# 4ch_lpc.net
KiCad netlist of a schematic drawn in EAGLE
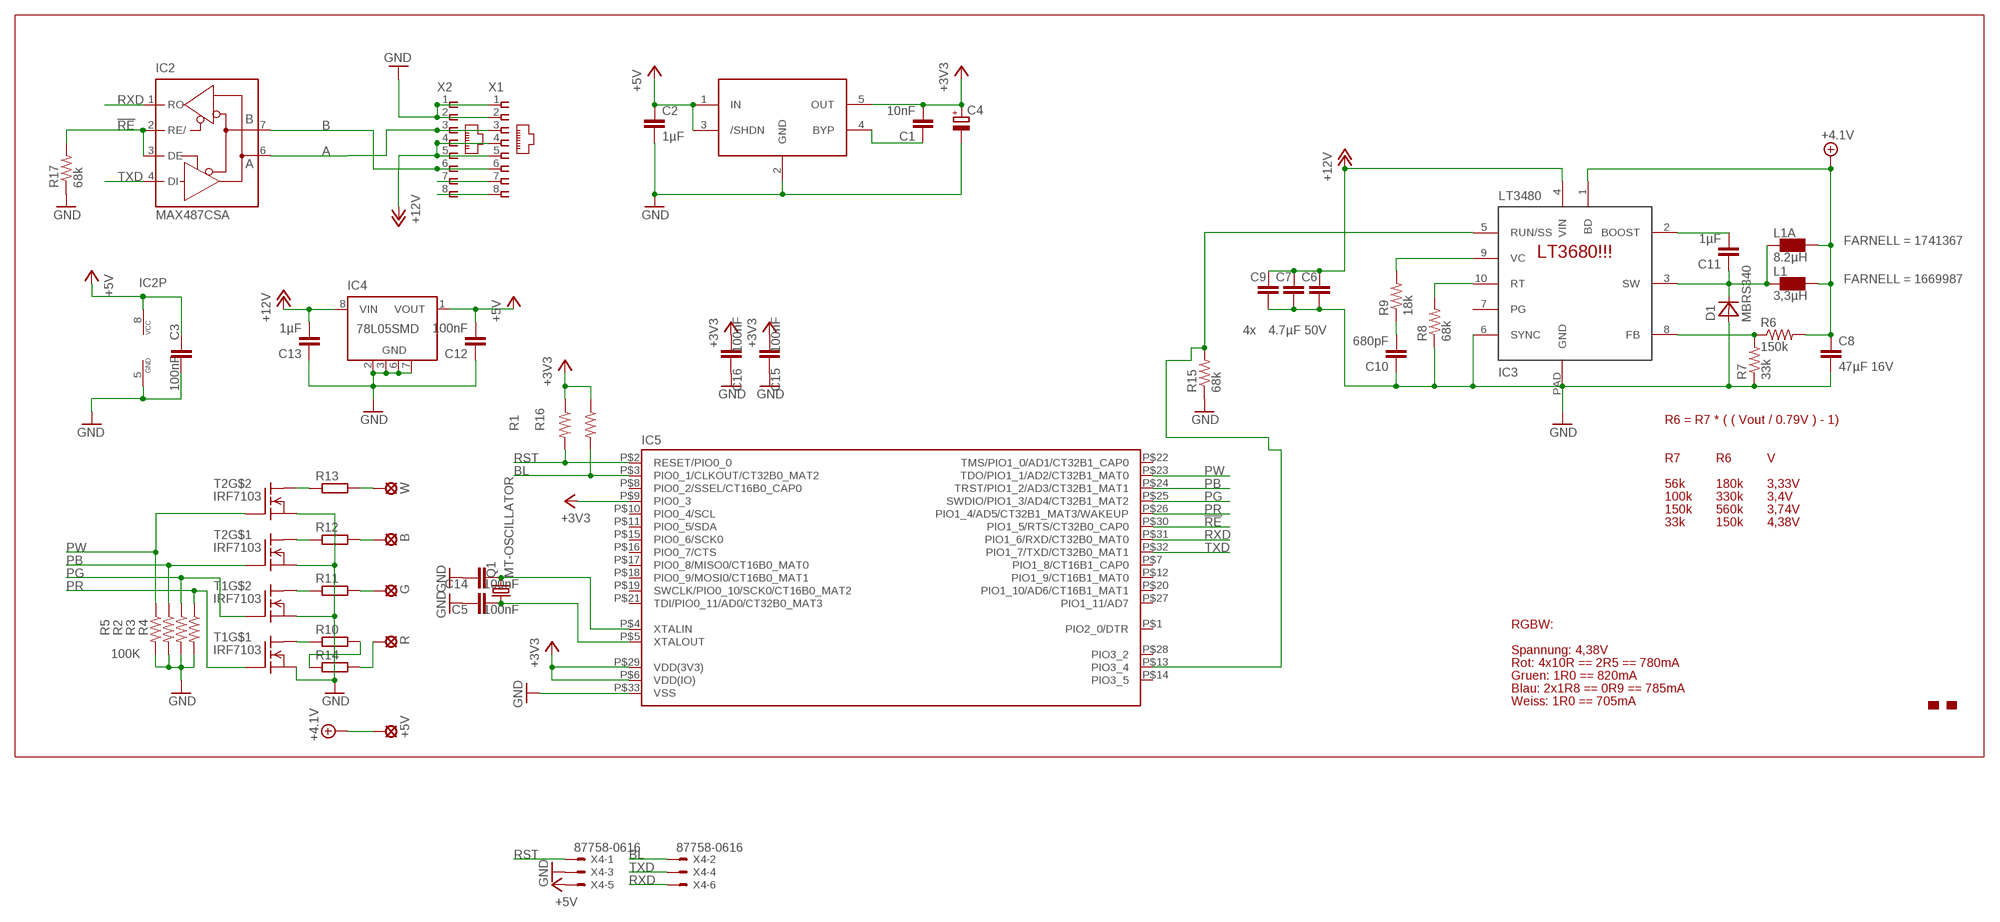
[diagram p0: schematic, sheet 1]

(export (version "E")
  (design (tool "Eeschema 10.0.6"))
  (components
    (comp (ref "+5V")
      (value "SE14")
      (footprint "eagle-import:SE14")
      (libsource (lib "eagle-import") (part "SE14"))
    )
    (comp (ref "B")
      (value "SE14")
      (footprint "eagle-import:SE14")
      (libsource (lib "eagle-import") (part "SE14"))
    )
    (comp (ref "C1")
      (value "10nF")
      (footprint "eagle-import:C0402")
      (libsource (lib "eagle-import") (part "C-EUC0402"))
    )
    (comp (ref "C2")
      (value "1µF")
      (footprint "eagle-import:0805")
      (libsource (lib "eagle-import") (part "SparkFun-Capacitors_CAP0805"))
    )
    (comp (ref "C3")
      (value "100nF")
      (footprint "eagle-import:0402-CAP")
      (libsource (lib "eagle-import") (part "CAP0402-CAP"))
    )
    (comp (ref "C4")
      (value "CPOL-EUSMCA")
      (footprint "eagle-import:SMC_A")
      (libsource (lib "eagle-import") (part "CPOL-EUSMCA"))
    )
    (comp (ref "C5")
      (value "100nF")
      (footprint "eagle-import:0402-CAP")
      (libsource (lib "eagle-import") (part "CAP0402-CAP"))
    )
    (comp (ref "C6")
      (value "4.7µF 50V")
      (footprint "eagle-import:1210")
      (libsource (lib "eagle-import") (part "CAP1210"))
    )
    (comp (ref "C7")
      (value "4.7µF 50V")
      (footprint "eagle-import:1210")
      (libsource (lib "eagle-import") (part "CAP1210"))
    )
    (comp (ref "C8")
      (value "47µF 16V")
      (footprint "eagle-import:1210")
      (libsource (lib "eagle-import") (part "CAP1210"))
    )
    (comp (ref "C9")
      (value "4.7µF 50V")
      (footprint "eagle-import:1210")
      (libsource (lib "eagle-import") (part "CAP1210"))
    )
    (comp (ref "C10")
      (value "680pF")
      (footprint "eagle-import:0805")
      (libsource (lib "eagle-import") (part "CAP0805"))
    )
    (comp (ref "C11")
      (value "1µF")
      (footprint "eagle-import:0805")
      (libsource (lib "eagle-import") (part "CAP0805"))
    )
    (comp (ref "C12")
      (value "100nF")
      (footprint "eagle-import:0402-CAP")
      (libsource (lib "eagle-import") (part "CAP0402-CAP"))
    )
    (comp (ref "C13")
      (value "1µF")
      (footprint "eagle-import:0805")
      (libsource (lib "eagle-import") (part "CAP0805"))
    )
    (comp (ref "C14")
      (value "100nF")
      (footprint "eagle-import:0402-CAP")
      (libsource (lib "eagle-import") (part "CAP0402-CAP"))
    )
    (comp (ref "C15")
      (value "100nF")
      (footprint "eagle-import:0402-CAP")
      (libsource (lib "eagle-import") (part "CAP0402-CAP"))
    )
    (comp (ref "C16")
      (value "100nF")
      (footprint "eagle-import:0402-CAP")
      (libsource (lib "eagle-import") (part "CAP0402-CAP"))
    )
    (comp (ref "D1")
      (value "MBRS340")
      (footprint "eagle-import:DO214AB")
      (libsource (lib "eagle-import") (part "MBRS340"))
    )
    (comp (ref "G")
      (value "SE14")
      (footprint "eagle-import:SE14")
      (libsource (lib "eagle-import") (part "SE14"))
    )
    (comp (ref "IC1")
      (value "LT1761")
      (footprint "eagle-import:SOT23-5L")
      (libsource (lib "eagle-import") (part "LT1761"))
    )
    (comp (ref "IC2")
      (value "MAX487CSA")
      (footprint "eagle-import:SO08")
      (fields (field (name "MF") "MAXIM") (field (name "MPN") "MAX481CSA"))
      (libsource (lib "eagle-import") (part "MAX481CSA"))
    )
    (comp (ref "IC3")
      (value "LT3972")
      (footprint "eagle-import:MSOP10-PAD")
      (libsource (lib "eagle-import") (part "LT3480"))
    )
    (comp (ref "IC4")
      (value "78L05SMD")
      (footprint "eagle-import:SO08")
      (libsource (lib "eagle-import") (part "78LSMD05"))
    )
    (comp (ref "IC5")
      (value "LPC1113/4_QFN")
      (footprint "eagle-import:HVQFN33-7X7")
      (fields (field (name "MANF") "NXP"))
      (libsource (lib "eagle-import") (part "LPC1113/4_QFN"))
    )
    (comp (ref "L1")
      (value "3,3µH")
      (footprint "eagle-import:RLF7030")
      (fields (field (name "FARNELL") "1669987"))
      (libsource (lib "eagle-import") (part "TDK_RLF7030"))
    )
    (comp (ref "L1A")
      (value "8.2µH")
      (footprint "eagle-import:IHLP-2525CZ")
      (fields (field (name "FARNELL") "1741367"))
      (libsource (lib "eagle-import") (part "IHLP-2525CZ"))
    )
    (comp (ref "Q1")
      (value "MT-OSCILLATOR")
      (footprint "eagle-import:MT")
      (libsource (lib "eagle-import") (part "MT-OSCILLATOR"))
    )
    (comp (ref "R")
      (value "SE14")
      (footprint "eagle-import:SE14")
      (libsource (lib "eagle-import") (part "SE14"))
    )
    (comp (ref "R1")
      (value "100K")
      (footprint "eagle-import:0402-RES")
      (libsource (lib "eagle-import") (part "RESISTOR0402-RES"))
    )
    (comp (ref "R2")
      (value "100K")
      (footprint "eagle-import:0402-RES")
      (libsource (lib "eagle-import") (part "RESISTOR0402-RES"))
    )
    (comp (ref "R3")
      (value "100K")
      (footprint "eagle-import:0402-RES")
      (libsource (lib "eagle-import") (part "RESISTOR0402-RES"))
    )
    (comp (ref "R4")
      (value "100K")
      (footprint "eagle-import:0402-RES")
      (libsource (lib "eagle-import") (part "RESISTOR0402-RES"))
    )
    (comp (ref "R5")
      (value "100K")
      (footprint "eagle-import:0402-RES")
      (libsource (lib "eagle-import") (part "RESISTOR0402-RES"))
    )
    (comp (ref "R6")
      (value "150k")
      (footprint "eagle-import:0805")
      (libsource (lib "eagle-import") (part "RESISTOR0805-RES"))
    )
    (comp (ref "R7")
      (value "33k")
      (footprint "eagle-import:0805")
      (libsource (lib "eagle-import") (part "RESISTOR0805-RES"))
    )
    (comp (ref "R8")
      (value "68k")
      (footprint "eagle-import:0805")
      (libsource (lib "eagle-import") (part "RESISTOR0805-RES"))
    )
    (comp (ref "R9")
      (value "18k")
      (footprint "eagle-import:0805")
      (libsource (lib "eagle-import") (part "RESISTOR0805-RES"))
    )
    (comp (ref "R10")
      (value "R-EU_MELF0207R")
      (footprint "eagle-import:MINI_MELF-0207R")
      (libsource (lib "eagle-import") (part "R-EU_MELF0207R"))
    )
    (comp (ref "R11")
      (value "R-EU_MELF0207R")
      (footprint "eagle-import:MINI_MELF-0207R")
      (libsource (lib "eagle-import") (part "R-EU_MELF0207R"))
    )
    (comp (ref "R12")
      (value "R-EU_MELF0207R")
      (footprint "eagle-import:MINI_MELF-0207R")
      (libsource (lib "eagle-import") (part "R-EU_MELF0207R"))
    )
    (comp (ref "R13")
      (value "R-EU_MELF0207R")
      (footprint "eagle-import:MINI_MELF-0207R")
      (libsource (lib "eagle-import") (part "R-EU_MELF0207R"))
    )
    (comp (ref "R14")
      (value "R-EU_MELF0207R")
      (footprint "eagle-import:MINI_MELF-0207R")
      (libsource (lib "eagle-import") (part "R-EU_MELF0207R"))
    )
    (comp (ref "R15")
      (value "68k")
      (footprint "eagle-import:0402-RES")
      (libsource (lib "eagle-import") (part "RESISTOR0402-RES"))
    )
    (comp (ref "R16")
      (value "100K")
      (footprint "eagle-import:0402-RES")
      (libsource (lib "eagle-import") (part "RESISTOR0402-RES"))
    )
    (comp (ref "R17")
      (value "68k")
      (footprint "eagle-import:0402-RES")
      (libsource (lib "eagle-import") (part "RESISTOR0402-RES"))
    )
    (comp (ref "T1")
      (value "IRF7103")
      (footprint "eagle-import:SO-8")
      (libsource (lib "eagle-import") (part "IRF7103"))
    )
    (comp (ref "T2")
      (value "IRF7103")
      (footprint "eagle-import:SO-8")
      (libsource (lib "eagle-import") (part "IRF7103"))
    )
    (comp (ref "U$1")
      (value "MAKE-DD_LOGO'PROMPT'")
      (footprint "eagle-import:MAKE-DD_LOGO_PROMPT")
      (libsource (lib "eagle-import") (part "MAKE-DD_LOGO'PROMPT'"))
    )
    (comp (ref "W")
      (value "SE14")
      (footprint "eagle-import:SE14")
      (libsource (lib "eagle-import") (part "SE14"))
    )
    (comp (ref "X1")
      (value "RJ45-8L-B")
      (footprint "eagle-import:RJ45-NO-SHIELD")
      (fields (field (name "MF") "TYCO ELECTRONICS"))
      (libsource (lib "eagle-import") (part "RJ45-8L-B"))
    )
    (comp (ref "X2")
      (value "RJ45-8L-B")
      (footprint "eagle-import:RJ45-NO-SHIELD")
      (fields (field (name "MF") "TYCO ELECTRONICS"))
      (libsource (lib "eagle-import") (part "RJ45-8L-B"))
    )
    (comp (ref "X4")
      (value "87758-0616")
      (footprint "eagle-import:87758-0616")
      (libsource (lib "eagle-import") (part "87758-0616"))
    )
  )
  (nets
    (net (code "1") (name "+3V3") (class "Default")
      (node (ref "C1") (pin "2") (pinfunction "2_2") (pintype "passive"))
      (node (ref "C15") (pin "2") (pinfunction "2_2") (pintype "passive"))
      (node (ref "C16") (pin "2") (pinfunction "2_2") (pintype "passive"))
      (node (ref "C4") (pin "+") (pinfunction "+_+") (pintype "passive"))
      (node (ref "IC1") (pin "5") (pinfunction "OUT_5") (pintype "bidirectional"))
      (node (ref "IC5") (pin "P$29") (pinfunction "VDD(3V3)_P$29") (pintype "power_in"))
      (node (ref "IC5") (pin "P$6") (pinfunction "VDD(IO)_P$6") (pintype "power_in"))
      (node (ref "IC5") (pin "P$9") (pinfunction "PIO0_3_P$9") (pintype "bidirectional"))
      (node (ref "R1") (pin "1") (pinfunction "1_1") (pintype "passive"))
      (node (ref "R16") (pin "1") (pinfunction "1_1") (pintype "passive"))
    )
    (net (code "2") (name "+4.1V") (class "Default")
      (node (ref "+5V") (pin "MP") (pinfunction "MP_MP") (pintype "passive"))
      (node (ref "C8") (pin "1") (pinfunction "1_1") (pintype "passive"))
      (node (ref "IC3") (pin "1") (pinfunction "BD_1") (pintype "bidirectional"))
      (node (ref "L1") (pin "P$1") (pinfunction "1_P$1") (pintype "passive"))
      (node (ref "L1A") (pin "P$1") (pinfunction "1_P$1") (pintype "passive"))
      (node (ref "R6") (pin "2") (pinfunction "2_2") (pintype "passive"))
    )
    (net (code "3") (name "+5V") (class "Default")
      (node (ref "C12") (pin "2") (pinfunction "2_2") (pintype "passive"))
      (node (ref "C2") (pin "1") (pinfunction "1_1") (pintype "passive"))
      (node (ref "C3") (pin "1") (pinfunction "1_1") (pintype "passive"))
      (node (ref "IC1") (pin "1") (pinfunction "IN_1") (pintype "bidirectional"))
      (node (ref "IC1") (pin "3") (pinfunction "/SHDN_3") (pintype "bidirectional"))
      (node (ref "IC2") (pin "8") (pinfunction "VCC_8") (pintype "power_in"))
      (node (ref "IC4") (pin "1") (pinfunction "VOUT_1") (pintype "output"))
      (node (ref "X4") (pin "5") (pinfunction "S_5") (pintype "passive"))
    )
    (net (code "4") (name "+12V") (class "Default")
      (node (ref "C13") (pin "2") (pinfunction "2_2") (pintype "passive"))
      (node (ref "C6") (pin "1") (pinfunction "1_1") (pintype "passive"))
      (node (ref "C7") (pin "1") (pinfunction "1_1") (pintype "passive"))
      (node (ref "C9") (pin "1") (pinfunction "1_1") (pintype "passive"))
      (node (ref "IC3") (pin "4") (pinfunction "VIN_4") (pintype "bidirectional"))
      (node (ref "IC4") (pin "8") (pinfunction "VIN_8") (pintype "passive"))
      (node (ref "X1") (pin "4") (pinfunction "4_4") (pintype "passive"))
      (node (ref "X1") (pin "5") (pinfunction "5_5") (pintype "passive"))
      (node (ref "X2") (pin "4") (pinfunction "4_4") (pintype "passive"))
      (node (ref "X2") (pin "5") (pinfunction "5_5") (pintype "passive"))
    )
    (net (code "5") (name "/A") (class "Default")
      (node (ref "IC2") (pin "6") (pinfunction "A_6") (pintype "passive"))
      (node (ref "X1") (pin "3") (pinfunction "3_3") (pintype "passive"))
      (node (ref "X2") (pin "3") (pinfunction "3_3") (pintype "passive"))
    )
    (net (code "6") (name "/B") (class "Default")
      (node (ref "IC2") (pin "7") (pinfunction "B_7") (pintype "passive"))
      (node (ref "X1") (pin "6") (pinfunction "6_6") (pintype "passive"))
      (node (ref "X2") (pin "6") (pinfunction "6_6") (pintype "passive"))
    )
    (net (code "7") (name "/BL") (class "Default")
      (node (ref "IC5") (pin "P$3") (pinfunction "PIO0_1/CLKOUT/CT32B0_MAT2_P$3") (pintype "bidirectional"))
      (node (ref "R16") (pin "2") (pinfunction "2_2") (pintype "passive"))
      (node (ref "X4") (pin "2") (pinfunction "S_2") (pintype "passive"))
    )
    (net (code "8") (name "/PB") (class "Default")
      (node (ref "IC5") (pin "P$24") (pinfunction "TRST/PIO1_2/AD3/CT32B1_MAT1_P$24") (pintype "bidirectional"))
      (node (ref "R2") (pin "1") (pinfunction "1_1") (pintype "passive"))
      (node (ref "T2") (pin "2") (pinfunction "G_2") (pintype "passive"))
    )
    (net (code "9") (name "/PG") (class "Default")
      (node (ref "IC5") (pin "P$25") (pinfunction "SWDIO/PIO1_3/AD4/CT32B1_MAT2_P$25") (pintype "bidirectional"))
      (node (ref "R3") (pin "1") (pinfunction "1_1") (pintype "passive"))
      (node (ref "T1") (pin "4") (pinfunction "G_4") (pintype "passive"))
    )
    (net (code "10") (name "/PR") (class "Default")
      (node (ref "IC5") (pin "P$26") (pinfunction "PIO1_4/AD5/CT32B1_MAT3/WAKEUP_P$26") (pintype "bidirectional"))
      (node (ref "R4") (pin "1") (pinfunction "1_1") (pintype "passive"))
      (node (ref "T1") (pin "2") (pinfunction "G_2") (pintype "passive"))
    )
    (net (code "11") (name "/PW") (class "Default")
      (node (ref "IC5") (pin "P$23") (pinfunction "TDO/PIO1_1/AD2/CT32B1_MAT0_P$23") (pintype "bidirectional"))
      (node (ref "R5") (pin "1") (pinfunction "1_1") (pintype "passive"))
      (node (ref "T2") (pin "4") (pinfunction "G_4") (pintype "passive"))
    )
    (net (code "12") (name "/RST") (class "Default")
      (node (ref "IC5") (pin "P$2") (pinfunction "RESET/PIO0_0_P$2") (pintype "bidirectional"))
      (node (ref "R1") (pin "2") (pinfunction "2_2") (pintype "passive"))
      (node (ref "X4") (pin "1") (pinfunction "S_1") (pintype "passive"))
    )
    (net (code "13") (name "/RXD") (class "Default")
      (node (ref "IC2") (pin "1") (pinfunction "RO_1") (pintype "output"))
      (node (ref "IC5") (pin "P$31") (pinfunction "PIO1_6/RXD/CT32B0_MAT0_P$31") (pintype "bidirectional"))
      (node (ref "X4") (pin "6") (pinfunction "S_6") (pintype "passive"))
    )
    (net (code "14") (name "/TXD") (class "Default")
      (node (ref "IC2") (pin "4") (pinfunction "DI_4") (pintype "input"))
      (node (ref "IC5") (pin "P$32") (pinfunction "PIO1_7/TXD/CT32B0_MAT1_P$32") (pintype "bidirectional"))
      (node (ref "X4") (pin "4") (pinfunction "S_4") (pintype "passive"))
    )
    (net (code "15") (name "/~{RE}") (class "Default")
      (node (ref "IC2") (pin "2") (pinfunction "RE/_2") (pintype "input"))
      (node (ref "IC2") (pin "3") (pinfunction "DE_3") (pintype "input"))
      (node (ref "IC5") (pin "P$30") (pinfunction "PIO1_5/RTS/CT32B0_CAP0_P$30") (pintype "bidirectional"))
      (node (ref "R17") (pin "2") (pinfunction "2_2") (pintype "passive"))
    )
    (net (code "16") (name "GND") (class "Default")
      (node (ref "C10") (pin "1") (pinfunction "1_1") (pintype "passive"))
      (node (ref "C12") (pin "1") (pinfunction "1_1") (pintype "passive"))
      (node (ref "C13") (pin "1") (pinfunction "1_1") (pintype "passive"))
      (node (ref "C14") (pin "1") (pinfunction "1_1") (pintype "passive"))
      (node (ref "C15") (pin "1") (pinfunction "1_1") (pintype "passive"))
      (node (ref "C16") (pin "1") (pinfunction "1_1") (pintype "passive"))
      (node (ref "C2") (pin "2") (pinfunction "2_2") (pintype "passive"))
      (node (ref "C3") (pin "2") (pinfunction "2_2") (pintype "passive"))
      (node (ref "C4") (pin "-") (pinfunction "-_-") (pintype "passive"))
      (node (ref "C5") (pin "1") (pinfunction "1_1") (pintype "passive"))
      (node (ref "C6") (pin "2") (pinfunction "2_2") (pintype "passive"))
      (node (ref "C7") (pin "2") (pinfunction "2_2") (pintype "passive"))
      (node (ref "C8") (pin "2") (pinfunction "2_2") (pintype "passive"))
      (node (ref "C9") (pin "2") (pinfunction "2_2") (pintype "passive"))
      (node (ref "D1") (pin "A") (pinfunction "A_A") (pintype "passive"))
      (node (ref "IC1") (pin "2") (pinfunction "GND_2") (pintype "bidirectional"))
      (node (ref "IC2") (pin "5") (pinfunction "GND_5") (pintype "power_in"))
      (node (ref "IC3") (pin "6") (pinfunction "SYNC_6") (pintype "bidirectional"))
      (node (ref "IC3") (pin "PAD") (pinfunction "GND_PAD") (pintype "bidirectional"))
      (node (ref "IC4") (pin "2") (pinfunction "GND_2") (pintype "power_in"))
      (node (ref "IC4") (pin "3") (pinfunction "GND_3") (pintype "power_in"))
      (node (ref "IC4") (pin "6") (pinfunction "GND_6") (pintype "power_in"))
      (node (ref "IC4") (pin "7") (pinfunction "GND_7") (pintype "power_in"))
      (node (ref "IC5") (pin "P$33") (pinfunction "VSS_P$33") (pintype "power_in"))
      (node (ref "R15") (pin "1") (pinfunction "1_1") (pintype "passive"))
      (node (ref "R17") (pin "1") (pinfunction "1_1") (pintype "passive"))
      (node (ref "R2") (pin "2") (pinfunction "2_2") (pintype "passive"))
      (node (ref "R3") (pin "2") (pinfunction "2_2") (pintype "passive"))
      (node (ref "R4") (pin "2") (pinfunction "2_2") (pintype "passive"))
      (node (ref "R5") (pin "2") (pinfunction "2_2") (pintype "passive"))
      (node (ref "R7") (pin "1") (pinfunction "1_1") (pintype "passive"))
      (node (ref "R8") (pin "1") (pinfunction "1_1") (pintype "passive"))
      (node (ref "T1") (pin "1") (pinfunction "S_1") (pintype "passive"))
      (node (ref "T1") (pin "3") (pinfunction "S_3") (pintype "passive"))
      (node (ref "T2") (pin "1") (pinfunction "S_1") (pintype "passive"))
      (node (ref "T2") (pin "3") (pinfunction "S_3") (pintype "passive"))
      (node (ref "X1") (pin "1") (pinfunction "1_1") (pintype "passive"))
      (node (ref "X1") (pin "2") (pinfunction "2_2") (pintype "passive"))
      (node (ref "X2") (pin "1") (pinfunction "1_1") (pintype "passive"))
      (node (ref "X2") (pin "2") (pinfunction "2_2") (pintype "passive"))
      (node (ref "X4") (pin "3") (pinfunction "S_3") (pintype "passive"))
    )
    (net (code "17") (name "Net-(B-PadMP)") (class "Default")
      (node (ref "B") (pin "MP") (pinfunction "MP_MP") (pintype "passive"))
      (node (ref "R12") (pin "2") (pinfunction "2_2") (pintype "passive"))
    )
    (net (code "18") (name "Net-(C10-Pad2)") (class "Default")
      (node (ref "C10") (pin "2") (pinfunction "2_2") (pintype "passive"))
      (node (ref "R9") (pin "1") (pinfunction "1_1") (pintype "passive"))
    )
    (net (code "19") (name "Net-(D1-C)") (class "Default")
      (node (ref "C11") (pin "1") (pinfunction "1_1") (pintype "passive"))
      (node (ref "D1") (pin "K") (pinfunction "C_K") (pintype "passive"))
      (node (ref "IC3") (pin "3") (pinfunction "SW_3") (pintype "bidirectional"))
      (node (ref "L1") (pin "P$2") (pinfunction "2_P$2") (pintype "passive"))
      (node (ref "L1A") (pin "P$2") (pinfunction "2_P$2") (pintype "passive"))
    )
    (net (code "20") (name "Net-(G-PadMP)") (class "Default")
      (node (ref "G") (pin "MP") (pinfunction "MP_MP") (pintype "passive"))
      (node (ref "R11") (pin "2") (pinfunction "2_2") (pintype "passive"))
    )
    (net (code "21") (name "Net-(IC1-BYP)") (class "Default")
      (node (ref "C1") (pin "1") (pinfunction "1_1") (pintype "passive"))
      (node (ref "IC1") (pin "4") (pinfunction "BYP_4") (pintype "bidirectional"))
    )
    (net (code "22") (name "Net-(IC3-BOOST)") (class "Default")
      (node (ref "C11") (pin "2") (pinfunction "2_2") (pintype "passive"))
      (node (ref "IC3") (pin "2") (pinfunction "BOOST_2") (pintype "bidirectional"))
    )
    (net (code "23") (name "Net-(IC3-FB)") (class "Default")
      (node (ref "IC3") (pin "8") (pinfunction "FB_8") (pintype "bidirectional"))
      (node (ref "R6") (pin "1") (pinfunction "1_1") (pintype "passive"))
      (node (ref "R7") (pin "2") (pinfunction "2_2") (pintype "passive"))
    )
    (net (code "24") (name "Net-(IC3-RT)") (class "Default")
      (node (ref "IC3") (pin "10") (pinfunction "RT_10") (pintype "bidirectional"))
      (node (ref "R8") (pin "2") (pinfunction "2_2") (pintype "passive"))
    )
    (net (code "25") (name "Net-(IC3-RUN{slash}SS)") (class "Default")
      (node (ref "IC3") (pin "5") (pinfunction "RUN/SS_5") (pintype "bidirectional"))
      (node (ref "IC5") (pin "P$13") (pinfunction "PIO3_4_P$13") (pintype "bidirectional"))
      (node (ref "R15") (pin "2") (pinfunction "2_2") (pintype "passive"))
    )
    (net (code "26") (name "Net-(IC3-VC)") (class "Default")
      (node (ref "IC3") (pin "9") (pinfunction "VC_9") (pintype "bidirectional"))
      (node (ref "R9") (pin "2") (pinfunction "2_2") (pintype "passive"))
    )
    (net (code "27") (name "Net-(IC5-XTALIN)") (class "Default")
      (node (ref "C14") (pin "2") (pinfunction "2_2") (pintype "passive"))
      (node (ref "IC5") (pin "P$4") (pinfunction "XTALIN_P$4") (pintype "input"))
      (node (ref "Q1") (pin "3") (pinfunction "2_3") (pintype "passive"))
    )
    (net (code "28") (name "Net-(IC5-XTALOUT)") (class "Default")
      (node (ref "C5") (pin "2") (pinfunction "2_2") (pintype "passive"))
      (node (ref "IC5") (pin "P$5") (pinfunction "XTALOUT_P$5") (pintype "output"))
      (node (ref "Q1") (pin "1") (pinfunction "1_1") (pintype "passive"))
    )
    (net (code "29") (name "Net-(R-PadMP)") (class "Default")
      (node (ref "R") (pin "MP") (pinfunction "MP_MP") (pintype "passive"))
      (node (ref "R14") (pin "2") (pinfunction "2_2") (pintype "passive"))
    )
    (net (code "30") (name "Net-(R10-Pad2)") (class "Default")
      (node (ref "R10") (pin "2") (pinfunction "2_2") (pintype "passive"))
      (node (ref "R14") (pin "1") (pinfunction "1_1") (pintype "passive"))
    )
    (net (code "31") (name "Net-(R13-Pad2)") (class "Default")
      (node (ref "R13") (pin "2") (pinfunction "2_2") (pintype "passive"))
      (node (ref "W") (pin "MP") (pinfunction "MP_MP") (pintype "passive"))
    )
    (net (code "32") (name "Net-(T1A-D1)") (class "Default")
      (node (ref "R10") (pin "1") (pinfunction "1_1") (pintype "passive"))
      (node (ref "T1") (pin "8") (pinfunction "D1_8") (pintype "passive"))
    )
    (net (code "33") (name "Net-(T1B-D1)") (class "Default")
      (node (ref "R11") (pin "1") (pinfunction "1_1") (pintype "passive"))
      (node (ref "T1") (pin "5") (pinfunction "D1_5") (pintype "passive"))
    )
    (net (code "34") (name "Net-(T2A-D1)") (class "Default")
      (node (ref "R12") (pin "1") (pinfunction "1_1") (pintype "passive"))
      (node (ref "T2") (pin "8") (pinfunction "D1_8") (pintype "passive"))
    )
    (net (code "35") (name "Net-(T2B-D1)") (class "Default")
      (node (ref "R13") (pin "1") (pinfunction "1_1") (pintype "passive"))
      (node (ref "T2") (pin "5") (pinfunction "D1_5") (pintype "passive"))
    )
    (net (code "36") (name "Net-(X1-Pad7)") (class "Default")
      (node (ref "X1") (pin "7") (pinfunction "7_7") (pintype "passive"))
      (node (ref "X2") (pin "7") (pinfunction "7_7") (pintype "passive"))
    )
    (net (code "37") (name "Net-(X1-Pad8)") (class "Default")
      (node (ref "X1") (pin "8") (pinfunction "8_8") (pintype "passive"))
      (node (ref "X2") (pin "8") (pinfunction "8_8") (pintype "passive"))
    )
    (net (code "38") (name "unconnected-(IC3-PG-Pad7)") (class "Default")
      (node (ref "IC3") (pin "7") (pinfunction "PG_7") (pintype "bidirectional"))
    )
    (net (code "39") (name "unconnected-(IC5-PIO0_2{slash}SSEL{slash}CT16B0_CAP0-PadP$8)") (class "Default")
      (node (ref "IC5") (pin "P$8") (pinfunction "PIO0_2/SSEL/CT16B0_CAP0_P$8") (pintype "bidirectional"))
    )
    (net (code "40") (name "unconnected-(IC5-PIO0_4{slash}SCL-PadP$10)") (class "Default")
      (node (ref "IC5") (pin "P$10") (pinfunction "PIO0_4/SCL_P$10") (pintype "bidirectional"))
    )
    (net (code "41") (name "unconnected-(IC5-PIO0_5{slash}SDA-PadP$11)") (class "Default")
      (node (ref "IC5") (pin "P$11") (pinfunction "PIO0_5/SDA_P$11") (pintype "bidirectional"))
    )
    (net (code "42") (name "unconnected-(IC5-PIO0_6{slash}SCK0-PadP$15)") (class "Default")
      (node (ref "IC5") (pin "P$15") (pinfunction "PIO0_6/SCK0_P$15") (pintype "bidirectional"))
    )
    (net (code "43") (name "unconnected-(IC5-PIO0_7{slash}CTS-PadP$16)") (class "Default")
      (node (ref "IC5") (pin "P$16") (pinfunction "PIO0_7/CTS_P$16") (pintype "bidirectional"))
    )
    (net (code "44") (name "unconnected-(IC5-PIO0_8{slash}MISO0{slash}CT16B0_MAT0-PadP$17)") (class "Default")
      (node (ref "IC5") (pin "P$17") (pinfunction "PIO0_8/MISO0/CT16B0_MAT0_P$17") (pintype "bidirectional"))
    )
    (net (code "45") (name "unconnected-(IC5-PIO0_9{slash}MOSI0{slash}CT16B0_MAT1-PadP$18)") (class "Default")
      (node (ref "IC5") (pin "P$18") (pinfunction "PIO0_9/MOSI0/CT16B0_MAT1_P$18") (pintype "bidirectional"))
    )
    (net (code "46") (name "unconnected-(IC5-PIO1_8{slash}CT16B1_CAP0-PadP$7)") (class "Default")
      (node (ref "IC5") (pin "P$7") (pinfunction "PIO1_8/CT16B1_CAP0_P$7") (pintype "bidirectional"))
    )
    (net (code "47") (name "unconnected-(IC5-PIO1_9{slash}CT16B1_MAT0-PadP$12)") (class "Default")
      (node (ref "IC5") (pin "P$12") (pinfunction "PIO1_9/CT16B1_MAT0_P$12") (pintype "bidirectional"))
    )
    (net (code "48") (name "unconnected-(IC5-PIO1_10{slash}AD6{slash}CT16B1_MAT1-PadP$20)") (class "Default")
      (node (ref "IC5") (pin "P$20") (pinfunction "PIO1_10/AD6/CT16B1_MAT1_P$20") (pintype "bidirectional"))
    )
    (net (code "49") (name "unconnected-(IC5-PIO1_11{slash}AD7-PadP$27)") (class "Default")
      (node (ref "IC5") (pin "P$27") (pinfunction "PIO1_11/AD7_P$27") (pintype "bidirectional"))
    )
    (net (code "50") (name "unconnected-(IC5-PIO2_0{slash}DTR-PadP$1)") (class "Default")
      (node (ref "IC5") (pin "P$1") (pinfunction "PIO2_0/DTR_P$1") (pintype "bidirectional"))
    )
    (net (code "51") (name "unconnected-(IC5-PIO3_2-PadP$28)") (class "Default")
      (node (ref "IC5") (pin "P$28") (pinfunction "PIO3_2_P$28") (pintype "bidirectional"))
    )
    (net (code "52") (name "unconnected-(IC5-PIO3_5-PadP$14)") (class "Default")
      (node (ref "IC5") (pin "P$14") (pinfunction "PIO3_5_P$14") (pintype "bidirectional"))
    )
    (net (code "53") (name "unconnected-(IC5-SWCLK{slash}PIO0_10{slash}SCK0{slash}CT16B0_MAT2-PadP$19)") (class "Default")
      (node (ref "IC5") (pin "P$19") (pinfunction "SWCLK/PIO0_10/SCK0/CT16B0_MAT2_P$19") (pintype "bidirectional"))
    )
    (net (code "54") (name "unconnected-(IC5-TDI{slash}PIO0_11{slash}AD0{slash}CT32B0_MAT3-PadP$21)") (class "Default")
      (node (ref "IC5") (pin "P$21") (pinfunction "TDI/PIO0_11/AD0/CT32B0_MAT3_P$21") (pintype "bidirectional"))
    )
    (net (code "55") (name "unconnected-(IC5-TMS{slash}PIO1_0{slash}AD1{slash}CT32B1_CAP0-PadP$22)") (class "Default")
      (node (ref "IC5") (pin "P$22") (pinfunction "TMS/PIO1_0/AD1/CT32B1_CAP0_P$22") (pintype "bidirectional"))
    )
    (net (code "56") (name "unconnected-(T1A-D-Pad7)") (class "Default")
      (node (ref "T1") (pin "7") (pinfunction "D_7") (pintype "passive"))
    )
    (net (code "57") (name "unconnected-(T1B-D-Pad6)") (class "Default")
      (node (ref "T1") (pin "6") (pinfunction "D_6") (pintype "passive"))
    )
    (net (code "58") (name "unconnected-(T2A-D-Pad7)") (class "Default")
      (node (ref "T2") (pin "7") (pinfunction "D_7") (pintype "passive"))
    )
    (net (code "59") (name "unconnected-(T2B-D-Pad6)") (class "Default")
      (node (ref "T2") (pin "6") (pinfunction "D_6") (pintype "passive"))
    )
  )
)
